# relay_board_mech.net
KiCad netlist of a schematic drawn in EAGLE
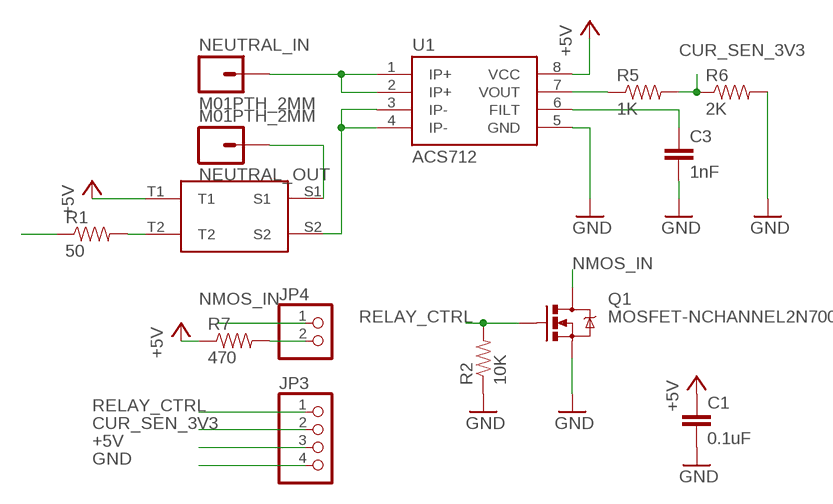
[diagram p0: schematic, sheet 1]

(export (version "E")
  (design (tool "Eeschema 10.0.6"))
  (components
    (comp (ref "C1")
      (value "0.1uF")
      (footprint "eagle-import:CAP-PTH-SMALLEZ")
      (libsource (lib "eagle-import") (part "CAPEZ"))
    )
    (comp (ref "C3")
      (value "1nF")
      (footprint "eagle-import:CAP-PTH-SMALLEZ")
      (libsource (lib "eagle-import") (part "CAPEZ"))
    )
    (comp (ref "JP3")
      (value "PINHD-1X4")
      (footprint "eagle-import:1X04")
      (libsource (lib "eagle-import") (part "PINHD-1X4"))
    )
    (comp (ref "JP4")
      (value "PINHD-1X2")
      (footprint "eagle-import:1X02")
      (libsource (lib "eagle-import") (part "PINHD-1X2"))
    )
    (comp (ref "NEUTRAL_IN")
      (value "M01PTH_2MM")
      (footprint "eagle-import:1X01_2MM")
      (libsource (lib "eagle-import") (part "M01PTH_2MM"))
    )
    (comp (ref "NEUTRAL_OUT")
      (value "M01PTH_2MM")
      (footprint "eagle-import:1X01_2MM")
      (libsource (lib "eagle-import") (part "M01PTH_2MM"))
    )
    (comp (ref "Q1")
      (value "MOSFET-NCHANNEL2N7000")
      (footprint "eagle-import:TO-92")
      (libsource (lib "eagle-import") (part "MOSFET-NCHANNEL2N7000"))
    )
    (comp (ref "R1")
      (value "50")
      (footprint "eagle-import:AXIAL-0.1")
      (libsource (lib "eagle-import") (part "10KOHM1/6W5%(PTH)VERTICAL"))
    )
    (comp (ref "R2")
      (value "10K")
      (footprint "eagle-import:AXIAL-0.1")
      (libsource (lib "eagle-import") (part "10KOHM1/6W5%(PTH)VERTICAL"))
    )
    (comp (ref "R5")
      (value "1K")
      (footprint "eagle-import:AXIAL-0.1")
      (libsource (lib "eagle-import") (part "10KOHM1/6W5%(PTH)VERTICAL"))
    )
    (comp (ref "R6")
      (value "2K")
      (footprint "eagle-import:AXIAL-0.1")
      (libsource (lib "eagle-import") (part "10KOHM1/6W5%(PTH)VERTICAL"))
    )
    (comp (ref "R7")
      (value "470")
      (footprint "eagle-import:AXIAL-0.1")
      (libsource (lib "eagle-import") (part "10KOHM1/6W5%(PTH)VERTICAL"))
    )
    (comp (ref "U$1")
      (value "T77S1D10-05")
      (footprint "eagle-import:T77S1D10-05")
      (libsource (lib "eagle-import") (part "T77S1D10-05"))
    )
    (comp (ref "U1")
      (value "ACS712")
      (footprint "eagle-import:SO08")
      (libsource (lib "eagle-import") (part "ACS712"))
    )
  )
  (nets
    (net (code "1") (name "+5V") (class "Default")
      (node (ref "C1") (pin "1") (pinfunction "1_1") (pintype "passive"))
      (node (ref "JP3") (pin "3") (pinfunction "3_3") (pintype "passive"))
      (node (ref "R7") (pin "P$1") (pinfunction "1_P$1") (pintype "passive"))
      (node (ref "U$1") (pin "T1") (pinfunction "T1_T1") (pintype "bidirectional"))
      (node (ref "U1") (pin "8") (pinfunction "VCC_8") (pintype "bidirectional"))
    )
    (net (code "2") (name "/CUR_SEN_3V3") (class "Default")
      (node (ref "JP3") (pin "2") (pinfunction "2_2") (pintype "passive"))
      (node (ref "R5") (pin "P$2") (pinfunction "2_P$2") (pintype "passive"))
      (node (ref "R6") (pin "P$1") (pinfunction "1_P$1") (pintype "passive"))
    )
    (net (code "3") (name "/NMOS_IN") (class "Default")
      (node (ref "JP4") (pin "1") (pinfunction "1_1") (pintype "passive"))
      (node (ref "Q1") (pin "3") (pinfunction "D_3") (pintype "passive"))
      (node (ref "R1") (pin "P$1") (pinfunction "1_P$1") (pintype "passive"))
    )
    (net (code "4") (name "/RELAY_CTRL") (class "Default")
      (node (ref "JP3") (pin "1") (pinfunction "1_1") (pintype "passive"))
      (node (ref "Q1") (pin "2") (pinfunction "G_2") (pintype "passive"))
      (node (ref "R2") (pin "P$2") (pinfunction "2_P$2") (pintype "passive"))
    )
    (net (code "5") (name "GND") (class "Default")
      (node (ref "C1") (pin "2") (pinfunction "2_2") (pintype "passive"))
      (node (ref "C3") (pin "2") (pinfunction "2_2") (pintype "passive"))
      (node (ref "JP3") (pin "4") (pinfunction "4_4") (pintype "passive"))
      (node (ref "Q1") (pin "1") (pinfunction "S_1") (pintype "passive"))
      (node (ref "R2") (pin "P$1") (pinfunction "1_P$1") (pintype "passive"))
      (node (ref "R6") (pin "P$2") (pinfunction "2_P$2") (pintype "passive"))
      (node (ref "U1") (pin "5") (pinfunction "GND_5") (pintype "bidirectional"))
    )
    (net (code "6") (name "Net-(NEUTRAL_IN-Pad1)") (class "Default")
      (node (ref "NEUTRAL_IN") (pin "1") (pinfunction "1_1") (pintype "passive"))
      (node (ref "U1") (pin "1") (pinfunction "IP+_1") (pintype "bidirectional"))
      (node (ref "U1") (pin "2") (pinfunction "IP+_2") (pintype "bidirectional"))
    )
    (net (code "7") (name "Net-(NEUTRAL_OUT-Pad1)") (class "Default")
      (node (ref "NEUTRAL_OUT") (pin "1") (pinfunction "1_1") (pintype "passive"))
      (node (ref "U$1") (pin "S1") (pinfunction "S1_S1") (pintype "bidirectional"))
    )
    (net (code "8") (name "Net-(R1-2)") (class "Default")
      (node (ref "R1") (pin "P$2") (pinfunction "2_P$2") (pintype "passive"))
      (node (ref "U$1") (pin "T2") (pinfunction "T2_T2") (pintype "bidirectional"))
    )
    (net (code "9") (name "Net-(R5-1)") (class "Default")
      (node (ref "R5") (pin "P$1") (pinfunction "1_P$1") (pintype "passive"))
      (node (ref "U1") (pin "7") (pinfunction "VOUT_7") (pintype "bidirectional"))
    )
    (net (code "10") (name "Net-(R7-2)") (class "Default")
      (node (ref "JP4") (pin "2") (pinfunction "2_2") (pintype "passive"))
      (node (ref "R7") (pin "P$2") (pinfunction "2_P$2") (pintype "passive"))
    )
    (net (code "11") (name "Net-(U$1-PadS2)") (class "Default")
      (node (ref "U$1") (pin "S2") (pinfunction "S2_S2") (pintype "bidirectional"))
      (node (ref "U1") (pin "3") (pinfunction "IP-_3") (pintype "bidirectional"))
      (node (ref "U1") (pin "4") (pinfunction "IP-_4") (pintype "bidirectional"))
    )
    (net (code "12") (name "Net-(U1-FILT)") (class "Default")
      (node (ref "C3") (pin "1") (pinfunction "1_1") (pintype "passive"))
      (node (ref "U1") (pin "6") (pinfunction "FILT_6") (pintype "bidirectional"))
    )
  )
)
